# DAC_AUX.net
KiCad netlist of a schematic drawn in Altium Designer
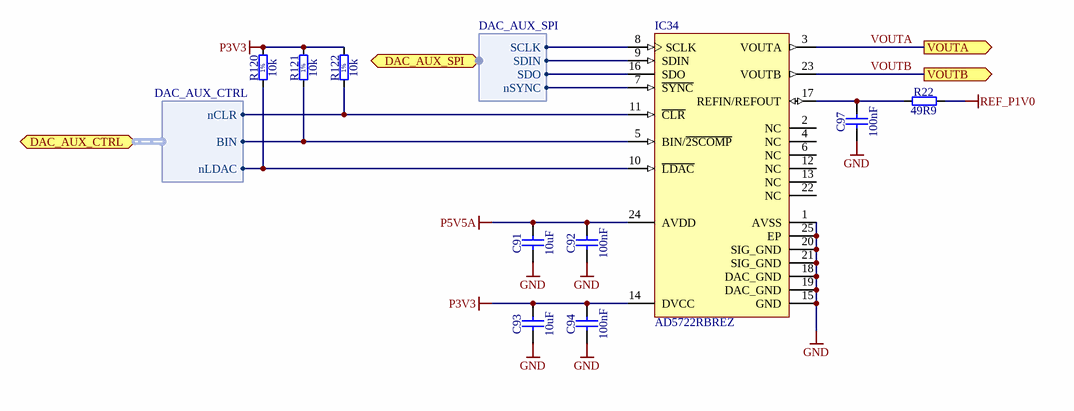
[diagram p0: DAC_AUX.SchDoc]

(export (version "E")
  (design (tool "Eeschema 10.0.6"))
  (components
    (comp (ref "C91")
      (value "10uF")
      (footprint "CAPC1608X80N")
      (description "Non-polarised capacitor")
      (fields
        (field (name "PART NUMBER") "CC0603_10UF_10V_10%_X5R")
        (field (name "VOLTAGE") "10V")
        (field (name "AUTHOR") "CERN DEM JLC")
      )
      (libsource (lib "Capacitors") (part "Capacitor - non polarized"))
    )
    (comp (ref "C92")
      (value "100nF")
      (footprint "CAPC1005X55N")
      (description "Non-polarised capacitor")
      (fields
        (field (name "PART NUMBER") "CC0402_100NF_16V_10%_X7R")
        (field (name "VOLTAGE") "16V")
        (field (name "AUTHOR") "CERN DEM JLC")
      )
      (libsource (lib "Capacitors") (part "Capacitor - non polarized"))
    )
    (comp (ref "C93")
      (value "10uF")
      (footprint "CAPC1608X80N")
      (description "Non-polarised capacitor")
      (fields
        (field (name "PART NUMBER") "CC0603_10UF_10V_10%_X5R")
        (field (name "VOLTAGE") "10V")
        (field (name "AUTHOR") "CERN DEM JLC")
      )
      (libsource (lib "Capacitors") (part "Capacitor - non polarized"))
    )
    (comp (ref "C94")
      (value "100nF")
      (footprint "CAPC1005X55N")
      (description "Non-polarised capacitor")
      (fields
        (field (name "PART NUMBER") "CC0402_100NF_16V_10%_X7R")
        (field (name "VOLTAGE") "16V")
        (field (name "AUTHOR") "CERN DEM JLC")
      )
      (libsource (lib "Capacitors") (part "Capacitor - non polarized"))
    )
    (comp (ref "C97")
      (value "100nF")
      (footprint "CAPC1005X55N")
      (description "Non-polarised capacitor")
      (fields
        (field (name "PART NUMBER") "CC0402_100NF_16V_10%_X7R")
        (field (name "VOLTAGE") "16V")
        (field (name "AUTHOR") "CERN DEM JLC")
      )
      (libsource (lib "Capacitors") (part "Capacitor - non polarized"))
    )
    (comp (ref "IC34")
      (value "AD5722RBREZ")
      (footprint "RE-24_N")
      (fields (field (name "GENERIC PART NUMBER") "AD5722R") (field (name "MANUFACTURER") "Analog Devices"))
      (libsource (lib "Altium Content Vault") (part "ADI-AD5722R-RE-24"))
    )
    (comp (ref "R22")
      (value "49R9")
      (footprint "RESC1005X40N")
      (description "Resistor - 1%")
      (fields
        (field (name "PART NUMBER") "R0402_49R9_1%_0.0625W_100PPM")
        (field (name "POWER") "0.0625W")
        (field (name "AUTHOR") "CERN DEM JLC")
      )
      (libsource (lib "Resistors") (part "Resistor - 1%"))
    )
    (comp (ref "R120")
      (value "10k")
      (footprint "RESC1005X40N")
      (description "Resistor - 1%")
      (fields
        (field (name "PART NUMBER") "R0402_10K_1%_0.0625W_100PPM")
        (field (name "MANUFACTURER") "GENERIC")
        (field (name "AUTHOR") "CERN DEM JLC")
      )
      (libsource (lib "Resistors") (part "Resistor - 1%"))
    )
    (comp (ref "R121")
      (value "10k")
      (footprint "RESC1005X40N")
      (description "Resistor - 1%")
      (fields
        (field (name "PART NUMBER") "R0402_10K_1%_0.0625W_100PPM")
        (field (name "MANUFACTURER") "GENERIC")
        (field (name "AUTHOR") "CERN DEM JLC")
      )
      (libsource (lib "Resistors") (part "Resistor - 1%"))
    )
    (comp (ref "R122")
      (value "10k")
      (footprint "RESC1005X40N")
      (description "Resistor - 1%")
      (fields
        (field (name "PART NUMBER") "R0402_10K_1%_0.0625W_100PPM")
        (field (name "MANUFACTURER") "GENERIC")
        (field (name "AUTHOR") "CERN DEM JLC")
      )
      (libsource (lib "Resistors") (part "Resistor - 1%"))
    )
  )
  (nets
    (net (code "3") (name "/BIN") (class "Default")
      (node (ref "IC34") (pin "5") (pinfunction "BIN/~{2SCOMP}_5") (pintype "input"))
      (node (ref "R121") (pin "1") (pinfunction "1_1") (pintype "passive"))
    )
    (net (code "4") (name "/SCLK") (class "Default")
      (node (ref "IC34") (pin "8") (pinfunction "SCLK_8") (pintype "input"))
    )
    (net (code "5") (name "/SDIN") (class "Default")
      (node (ref "IC34") (pin "9") (pinfunction "SDIN_9") (pintype "input"))
    )
    (net (code "6") (name "/SDO") (class "Default")
      (node (ref "IC34") (pin "16") (pinfunction "SDO_16") (pintype "tri_state"))
    )
    (net (code "7") (name "/VOUTA") (class "Default")
      (node (ref "IC34") (pin "3") (pinfunction "VOUTA_3") (pintype "output"))
    )
    (net (code "8") (name "/VOUTB") (class "Default")
      (node (ref "IC34") (pin "23") (pinfunction "VOUTB_23") (pintype "output"))
    )
    (net (code "9") (name "/nCLR") (class "Default")
      (node (ref "IC34") (pin "11") (pinfunction "~{CLR}_11") (pintype "input"))
      (node (ref "R122") (pin "1") (pinfunction "1_1") (pintype "passive"))
    )
    (net (code "10") (name "/nLDAC") (class "Default")
      (node (ref "IC34") (pin "10") (pinfunction "~{LDAC}_10") (pintype "input"))
      (node (ref "R120") (pin "1") (pinfunction "1_1") (pintype "passive"))
    )
    (net (code "11") (name "/nSYNC") (class "Default")
      (node (ref "IC34") (pin "7") (pinfunction "~{SYNC}_7") (pintype "input"))
    )
    (net (code "14") (name "GND") (class "Default")
      (node (ref "C91") (pin "1") (pinfunction "1_1") (pintype "passive"))
      (node (ref "C92") (pin "1") (pinfunction "1_1") (pintype "passive"))
      (node (ref "C93") (pin "1") (pinfunction "1_1") (pintype "passive"))
      (node (ref "C94") (pin "1") (pinfunction "1_1") (pintype "passive"))
      (node (ref "C97") (pin "1") (pinfunction "1_1") (pintype "passive"))
      (node (ref "IC34") (pin "1") (pinfunction "AVSS_1") (pintype "power_in"))
      (node (ref "IC34") (pin "15") (pinfunction "GND_15") (pintype "power_in"))
      (node (ref "IC34") (pin "18") (pinfunction "DAC_GND_18") (pintype "power_in"))
      (node (ref "IC34") (pin "19") (pinfunction "DAC_GND_19") (pintype "power_in"))
      (node (ref "IC34") (pin "20") (pinfunction "SIG_GND_20") (pintype "power_in"))
      (node (ref "IC34") (pin "21") (pinfunction "SIG_GND_21") (pintype "power_in"))
      (node (ref "IC34") (pin "25") (pinfunction "EP_25") (pintype "power_in"))
    )
    (net (code "15") (name "Net-(IC34-REFIN{slash}REFOUT)") (class "Default")
      (node (ref "C97") (pin "2") (pinfunction "2_2") (pintype "passive"))
      (node (ref "IC34") (pin "17") (pinfunction "REFIN/REFOUT_17") (pintype "bidirectional"))
      (node (ref "R22") (pin "1") (pinfunction "1_1") (pintype "passive"))
    )
    (net (code "16") (name "P3V3") (class "Default")
      (node (ref "C93") (pin "2") (pinfunction "2_2") (pintype "passive"))
      (node (ref "C94") (pin "2") (pinfunction "2_2") (pintype "passive"))
      (node (ref "IC34") (pin "14") (pinfunction "DVCC_14") (pintype "power_in"))
      (node (ref "R120") (pin "2") (pinfunction "2_2") (pintype "passive"))
      (node (ref "R121") (pin "2") (pinfunction "2_2") (pintype "passive"))
      (node (ref "R122") (pin "2") (pinfunction "2_2") (pintype "passive"))
    )
    (net (code "17") (name "P5V5A") (class "Default")
      (node (ref "C91") (pin "2") (pinfunction "2_2") (pintype "passive"))
      (node (ref "C92") (pin "2") (pinfunction "2_2") (pintype "passive"))
      (node (ref "IC34") (pin "24") (pinfunction "AVDD_24") (pintype "power_in"))
    )
    (net (code "18") (name "REF_P1V0") (class "Default")
      (node (ref "R22") (pin "2") (pinfunction "2_2") (pintype "passive"))
    )
    (net (code "19") (name "unconnected-(IC34-NC-Pad2)") (class "Default")
      (node (ref "IC34") (pin "2") (pinfunction "NC_2") (pintype "passive"))
    )
    (net (code "20") (name "unconnected-(IC34-NC-Pad4)") (class "Default")
      (node (ref "IC34") (pin "4") (pinfunction "NC_4") (pintype "passive"))
    )
    (net (code "21") (name "unconnected-(IC34-NC-Pad6)") (class "Default")
      (node (ref "IC34") (pin "6") (pinfunction "NC_6") (pintype "passive"))
    )
    (net (code "22") (name "unconnected-(IC34-NC-Pad12)") (class "Default")
      (node (ref "IC34") (pin "12") (pinfunction "NC_12") (pintype "passive"))
    )
    (net (code "23") (name "unconnected-(IC34-NC-Pad13)") (class "Default")
      (node (ref "IC34") (pin "13") (pinfunction "NC_13") (pintype "passive"))
    )
    (net (code "24") (name "unconnected-(IC34-NC-Pad22)") (class "Default")
      (node (ref "IC34") (pin "22") (pinfunction "NC_22") (pintype "passive"))
    )
  )
)
